# blink1_v2c3.net
KiCad netlist of a schematic drawn in EAGLE
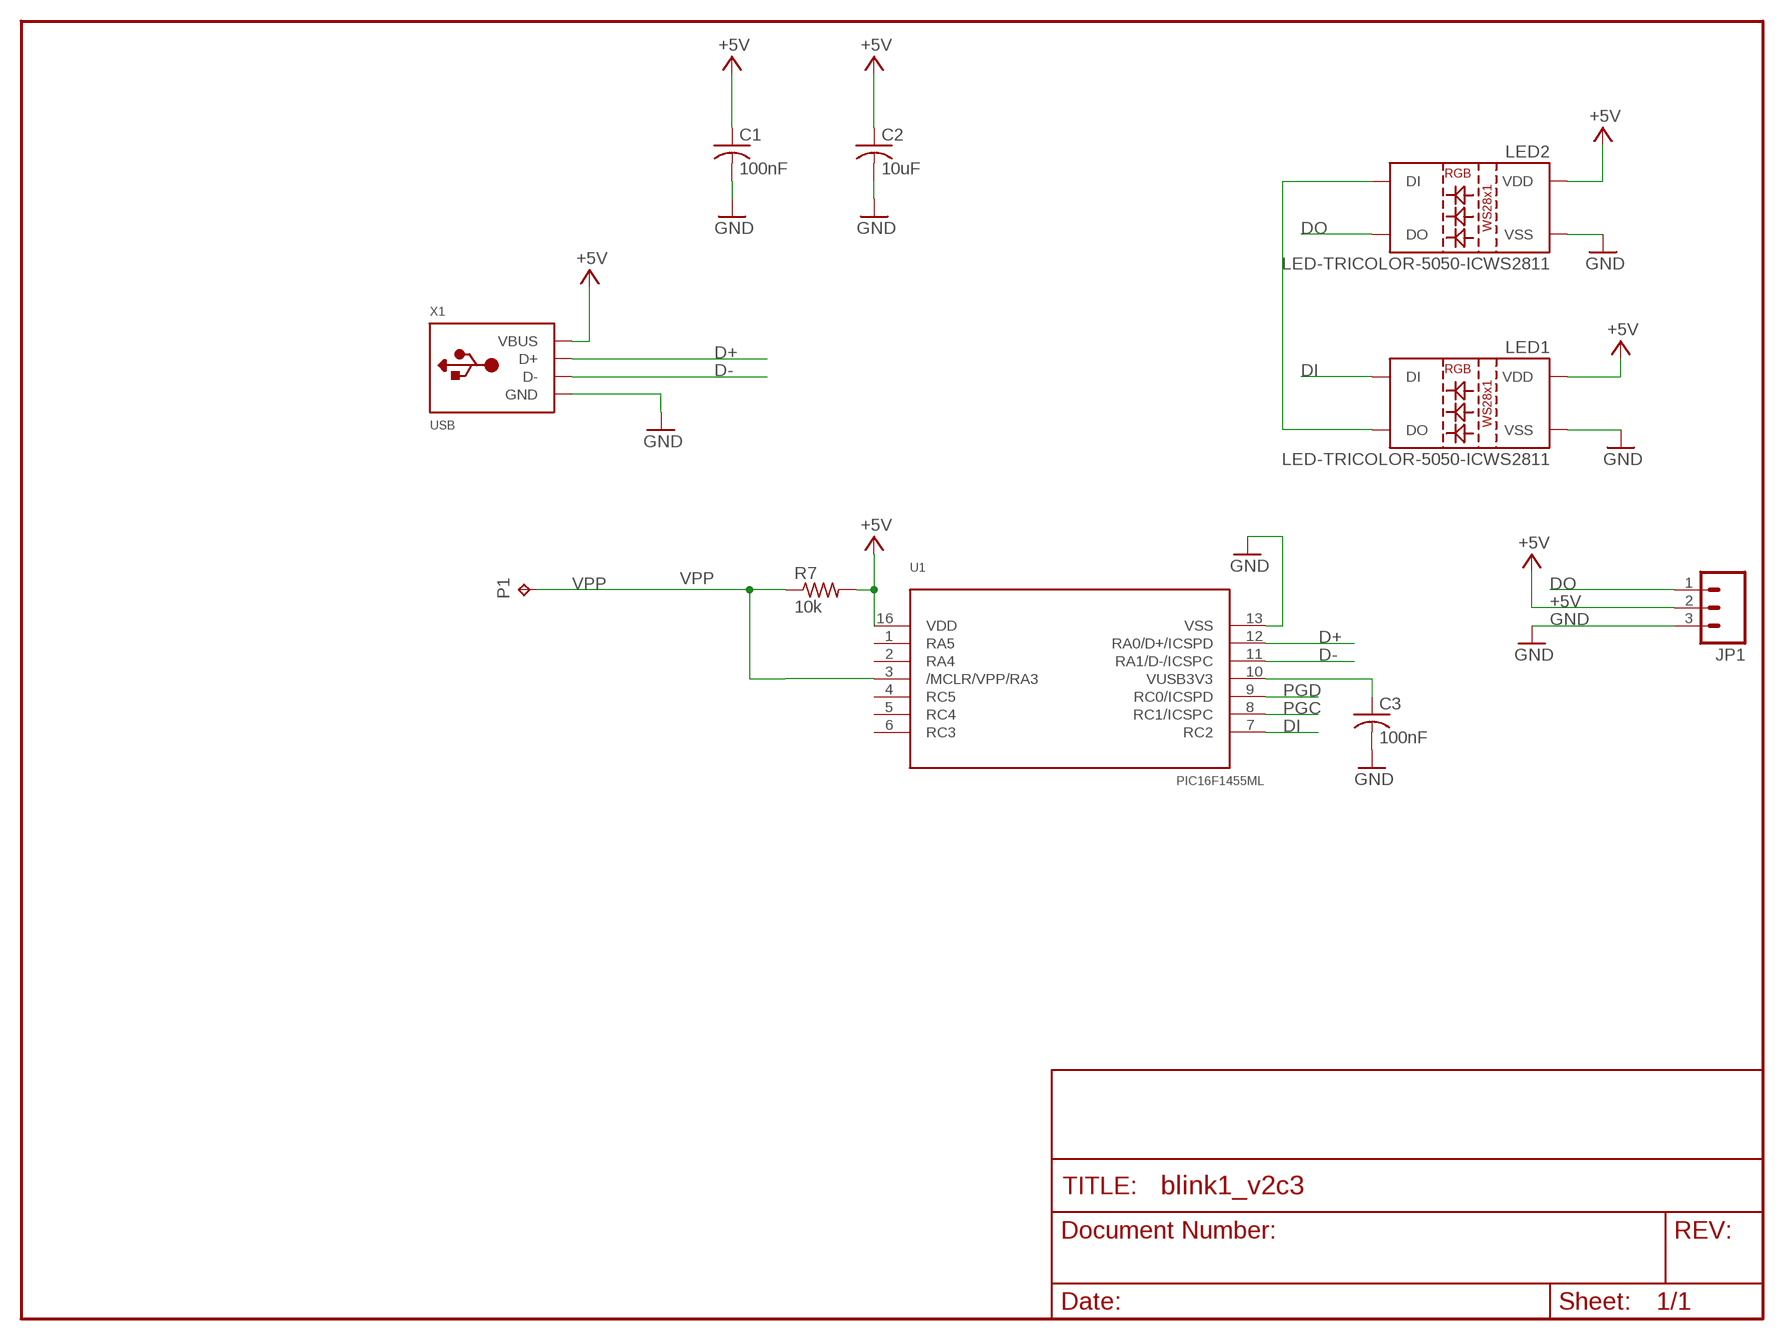
[diagram p0: schematic, sheet 1]

(export (version "E")
  (design (tool "Eeschema 10.0.6"))
  (components
    (comp (ref "C1")
      (value "100nF")
      (footprint "eagle-import:C0603")
      (libsource (lib "eagle-import") (part "C-USC0603"))
    )
    (comp (ref "C2")
      (value "10uF")
      (footprint "eagle-import:C0603")
      (libsource (lib "eagle-import") (part "C-USC0603"))
    )
    (comp (ref "C3")
      (value "100nF")
      (footprint "eagle-import:C0603")
      (libsource (lib "eagle-import") (part "C-USC0603"))
    )
    (comp (ref "JP1")
      (value "M03PTH")
      (footprint "eagle-import:1X03")
      (libsource (lib "eagle-import") (part "M03PTH"))
    )
    (comp (ref "LED1")
      (value "LED-TRICOLOR-5050-ICWS2811")
      (footprint "eagle-import:LED-TRICOLOR-5050-IC")
      (libsource (lib "eagle-import") (part "LED-TRICOLOR-5050-ICWS2811"))
    )
    (comp (ref "LED2")
      (value "LED-TRICOLOR-5050-ICWS2811")
      (footprint "eagle-import:LED-TRICOLOR-5050-IC")
      (libsource (lib "eagle-import") (part "LED-TRICOLOR-5050-ICWS2811"))
    )
    (comp (ref "P1")
      (value "TPTP11SQ")
      (footprint "eagle-import:TP11SQ")
      (libsource (lib "eagle-import") (part "TPTP11SQ"))
    )
    (comp (ref "R7")
      (value "10k")
      (footprint "eagle-import:R0603")
      (libsource (lib "eagle-import") (part "R-US_R0603"))
    )
    (comp (ref "U1")
      (value "PIC16F1455ML")
      (footprint "eagle-import:QFN16_4X4")
      (libsource (lib "eagle-import") (part "PIC16F1455ML"))
    )
    (comp (ref "X1")
      (value "USB")
      (footprint "eagle-import:MOLEX-48037-1000")
      (libsource (lib "eagle-import") (part "USB"))
    )
  )
  (nets
    (net (code "1") (name "+5V") (class "Default")
      (node (ref "C1") (pin "1") (pinfunction "1_1") (pintype "passive"))
      (node (ref "C2") (pin "1") (pinfunction "1_1") (pintype "passive"))
      (node (ref "JP1") (pin "2") (pinfunction "2_2") (pintype "passive"))
      (node (ref "LED1") (pin "3") (pinfunction "VDD_3") (pintype "bidirectional"))
      (node (ref "LED1") (pin "5") (pinfunction "VDD_5") (pintype "bidirectional"))
      (node (ref "LED2") (pin "3") (pinfunction "VDD_3") (pintype "bidirectional"))
      (node (ref "LED2") (pin "5") (pinfunction "VDD_5") (pintype "bidirectional"))
      (node (ref "R7") (pin "2") (pinfunction "2_2") (pintype "passive"))
      (node (ref "U1") (pin "16") (pinfunction "VDD_16") (pintype "bidirectional"))
      (node (ref "X1") (pin "1") (pinfunction "VBUS_1") (pintype "power_in"))
    )
    (net (code "2") (name "/D+") (class "Default")
      (node (ref "U1") (pin "12") (pinfunction "RA0/D+/ICSPD_12") (pintype "bidirectional"))
      (node (ref "X1") (pin "3") (pinfunction "D+_3") (pintype "bidirectional"))
    )
    (net (code "3") (name "/D-") (class "Default")
      (node (ref "U1") (pin "11") (pinfunction "RA1/D-/ICSPC_11") (pintype "bidirectional"))
      (node (ref "X1") (pin "2") (pinfunction "D-_2") (pintype "bidirectional"))
    )
    (net (code "4") (name "/DI") (class "Default")
      (node (ref "LED1") (pin "2") (pinfunction "DI_2") (pintype "bidirectional"))
      (node (ref "U1") (pin "7") (pinfunction "RC2_7") (pintype "bidirectional"))
    )
    (net (code "5") (name "/DO") (class "Default")
      (node (ref "JP1") (pin "1") (pinfunction "1_1") (pintype "passive"))
      (node (ref "LED2") (pin "1") (pinfunction "DO_1") (pintype "bidirectional"))
    )
    (net (code "6") (name "/PGC") (class "Default")
      (node (ref "U1") (pin "8") (pinfunction "RC1/ICSPC_8") (pintype "bidirectional"))
    )
    (net (code "7") (name "/PGD") (class "Default")
      (node (ref "U1") (pin "9") (pinfunction "RC0/ICSPD_9") (pintype "bidirectional"))
    )
    (net (code "8") (name "/VPP") (class "Default")
      (node (ref "P1") (pin "TP") (pinfunction "TP_TP") (pintype "input"))
      (node (ref "R7") (pin "1") (pinfunction "1_1") (pintype "passive"))
      (node (ref "U1") (pin "3") (pinfunction "/MCLR/VPP/RA3_3") (pintype "bidirectional"))
    )
    (net (code "9") (name "GND") (class "Default")
      (node (ref "C1") (pin "2") (pinfunction "2_2") (pintype "passive"))
      (node (ref "C2") (pin "2") (pinfunction "2_2") (pintype "passive"))
      (node (ref "C3") (pin "2") (pinfunction "2_2") (pintype "passive"))
      (node (ref "JP1") (pin "3") (pinfunction "3_3") (pintype "passive"))
      (node (ref "LED1") (pin "6") (pinfunction "VSS_6") (pintype "bidirectional"))
      (node (ref "LED2") (pin "6") (pinfunction "VSS_6") (pintype "bidirectional"))
      (node (ref "U1") (pin "13") (pinfunction "VSS_13") (pintype "bidirectional"))
      (node (ref "X1") (pin "4") (pinfunction "GND_4") (pintype "power_in"))
    )
    (net (code "10") (name "Net-(LED1-DO)") (class "Default")
      (node (ref "LED1") (pin "1") (pinfunction "DO_1") (pintype "bidirectional"))
      (node (ref "LED2") (pin "2") (pinfunction "DI_2") (pintype "bidirectional"))
    )
    (net (code "11") (name "Net-(U1-VUSB3V3)") (class "Default")
      (node (ref "C3") (pin "1") (pinfunction "1_1") (pintype "passive"))
      (node (ref "U1") (pin "10") (pinfunction "VUSB3V3_10") (pintype "bidirectional"))
    )
    (net (code "12") (name "unconnected-(U1-RA4-Pad2)") (class "Default")
      (node (ref "U1") (pin "2") (pinfunction "RA4_2") (pintype "bidirectional"))
    )
    (net (code "13") (name "unconnected-(U1-RA5-Pad1)") (class "Default")
      (node (ref "U1") (pin "1") (pinfunction "RA5_1") (pintype "bidirectional"))
    )
    (net (code "14") (name "unconnected-(U1-RC3-Pad6)") (class "Default")
      (node (ref "U1") (pin "6") (pinfunction "RC3_6") (pintype "bidirectional"))
    )
    (net (code "15") (name "unconnected-(U1-RC4-Pad5)") (class "Default")
      (node (ref "U1") (pin "5") (pinfunction "RC4_5") (pintype "bidirectional"))
    )
    (net (code "16") (name "unconnected-(U1-RC5-Pad4)") (class "Default")
      (node (ref "U1") (pin "4") (pinfunction "RC5_4") (pintype "bidirectional"))
    )
  )
)
